# Reset.net
KiCad netlist of a schematic drawn in Altium Designer
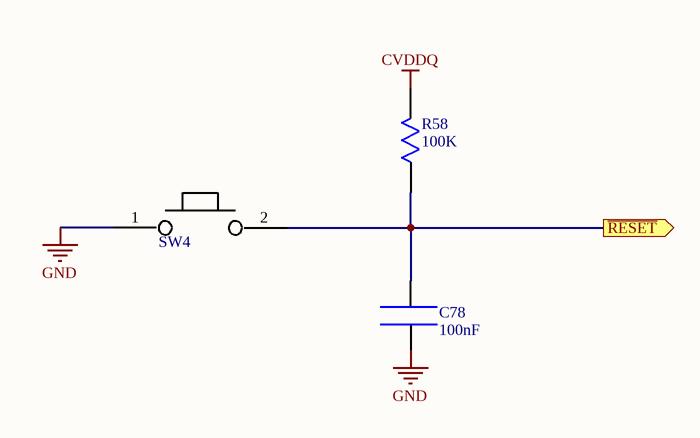
[diagram p0: Reset.SchDoc]

(export (version "E")
  (design (tool "Eeschema 10.0.6"))
  (components
    (comp (ref "C78")
      (value "100nF")
      (footprint "SMD Capacitor 0603")
      (fields (field (name "Comment") "Capacitor"))
      (libsource (lib "DA_Component_Library") (part "Capacitor"))
    )
    (comp (ref "R58")
      (value "100K")
      (footprint "SMD Resistor 0603")
      (fields (field (name "Comment") "Resistor"))
      (libsource (lib "DA_Component_Library") (part "Resistor"))
    )
    (comp (ref "SW4")
      (value "PB_Switch")
      (footprint "EVQPAC07K")
      (description "Push Button Switch")
      (libsource (lib "DA_Component_Library") (part "PB_Switch"))
    )
  )
  (nets
    (net (code "1") (name "/~{RESET}") (class "Default")
      (node (ref "C78") (pin "1") (pinfunction "1_1") (pintype "passive"))
      (node (ref "R58") (pin "0") (pinfunction "0_0") (pintype "passive"))
      (node (ref "SW4") (pin "2") (pinfunction "2_2") (pintype "passive"))
    )
    (net (code "2") (name "CVDDQ") (class "Default")
      (node (ref "R58") (pin "1") (pinfunction "1_1") (pintype "passive"))
    )
    (net (code "3") (name "GND") (class "Default")
      (node (ref "C78") (pin "0") (pinfunction "0_0") (pintype "passive"))
      (node (ref "SW4") (pin "1") (pinfunction "1_1") (pintype "passive"))
    )
  )
)
